# Solenoid_9.net
KiCad netlist of a schematic drawn in EAGLE
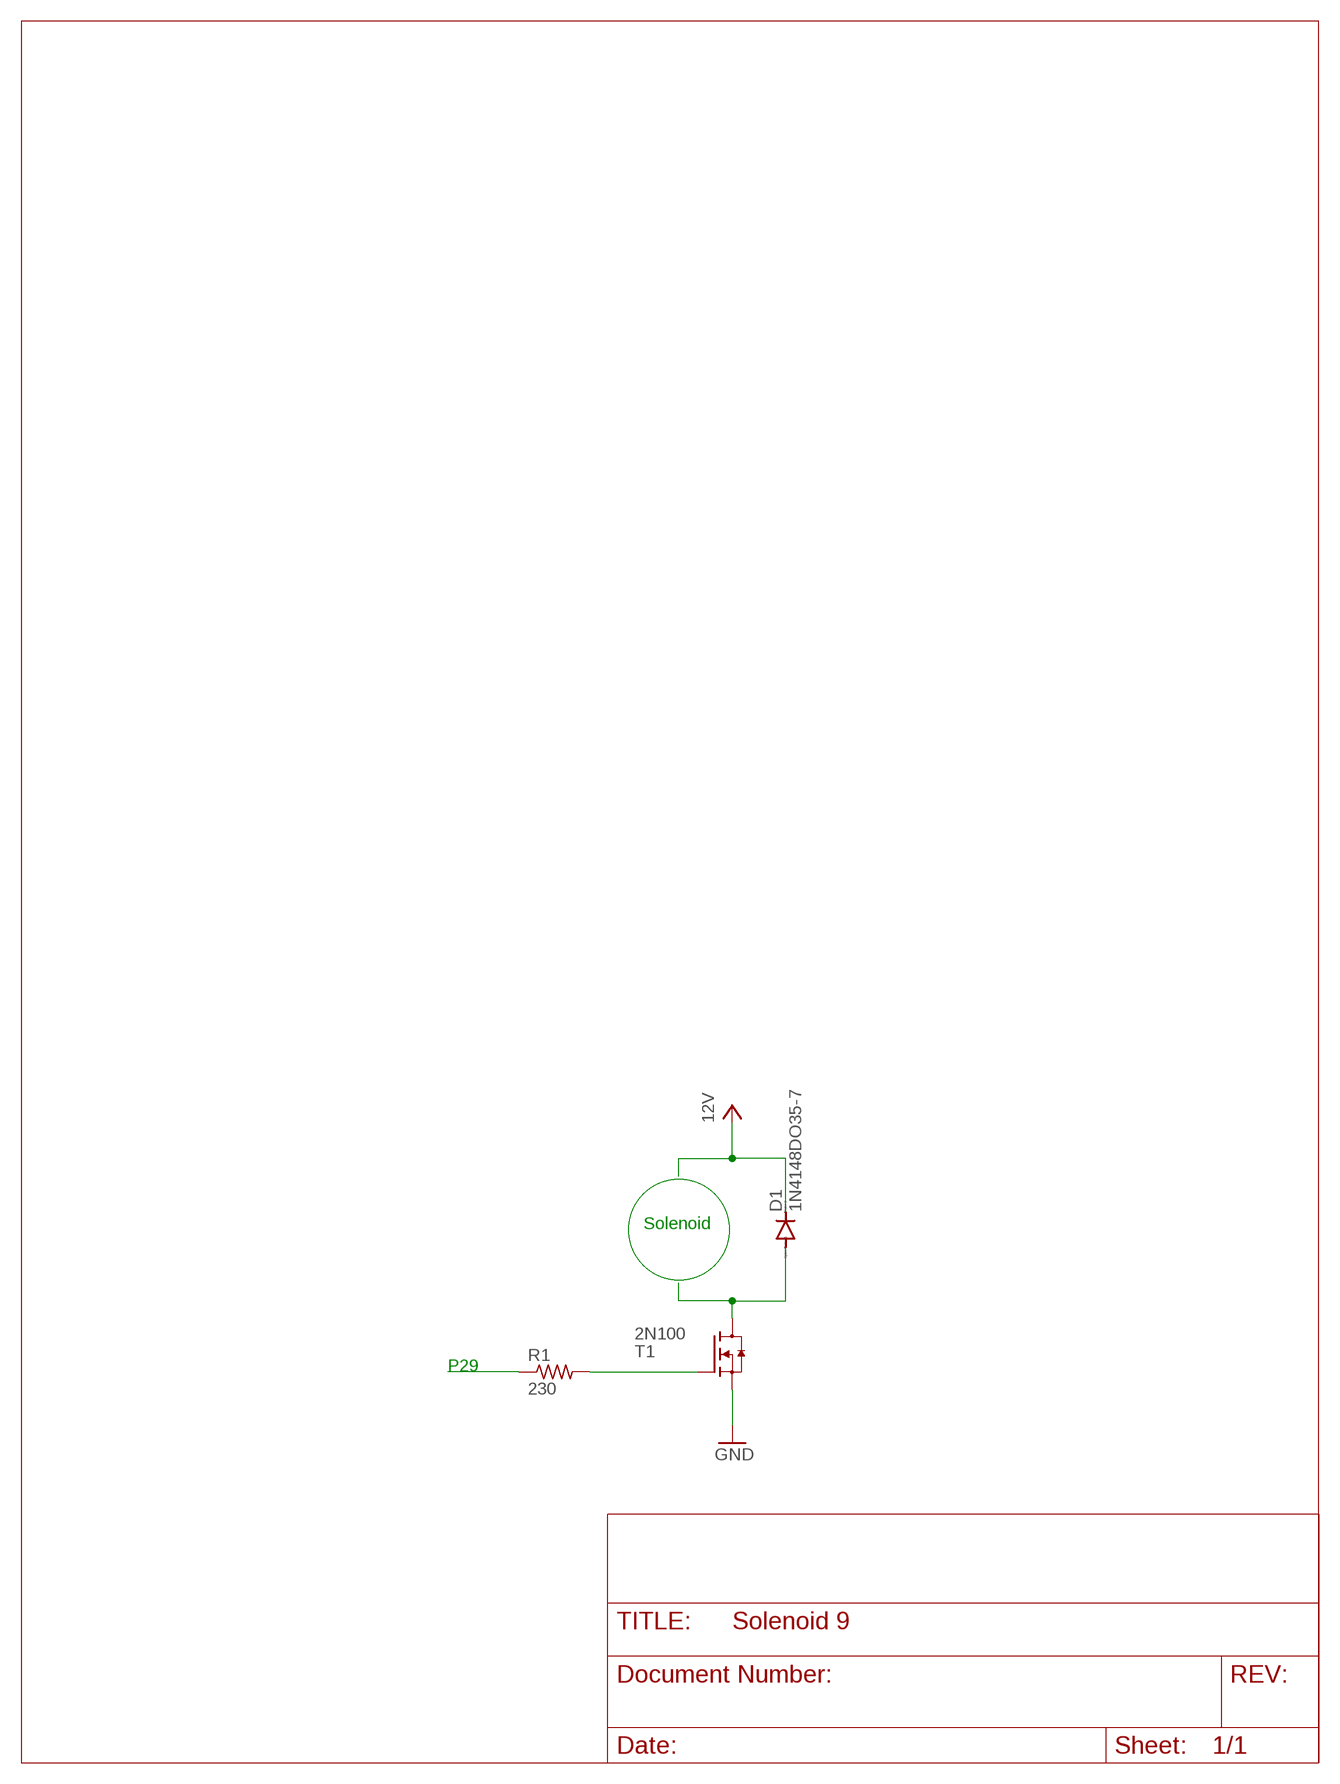
[diagram p0: schematic, sheet 1]

(export (version "E")
  (design (tool "Eeschema 10.0.6"))
  (components
    (comp (ref "D1")
      (value "1N4148DO35-7")
      (footprint "eagle-import:DO35-7")
      (libsource (lib "eagle-import") (part "1N4148DO35-7"))
    )
    (comp (ref "R1")
      (value "230")
      (footprint "eagle-import:0204_7")
      (libsource (lib "eagle-import") (part "R-US_0204/7"))
    )
    (comp (ref "T1")
      (value "2N100")
      (footprint "eagle-import:PG-TO263-7-3")
      (libsource (lib "eagle-import") (part "IPB180N06S4-H1"))
    )
  )
  (nets
    (net (code "1") (name "12V") (class "Default")
      (node (ref "D1") (pin "C") (pinfunction "C_C") (pintype "passive"))
    )
    (net (code "2") (name "GND") (class "Default")
      (node (ref "T1") (pin "2") (pinfunction "S_2") (pintype "passive"))
      (node (ref "T1") (pin "3") (pinfunction "S_3") (pintype "passive"))
      (node (ref "T1") (pin "5") (pinfunction "S_5") (pintype "passive"))
      (node (ref "T1") (pin "6") (pinfunction "S_6") (pintype "passive"))
      (node (ref "T1") (pin "7") (pinfunction "S_7") (pintype "passive"))
    )
    (net (code "3") (name "Net-(T1-D)") (class "Default")
      (node (ref "D1") (pin "A") (pinfunction "A_A") (pintype "passive"))
      (node (ref "T1") (pin "8") (pinfunction "D_8") (pintype "passive"))
    )
    (net (code "4") (name "Net-(T1-G)") (class "Default")
      (node (ref "R1") (pin "2") (pinfunction "2_2") (pintype "passive"))
      (node (ref "T1") (pin "1") (pinfunction "G_1") (pintype "passive"))
    )
    (net (code "5") (name "unconnected-(R1-Pad1)") (class "Default")
      (node (ref "R1") (pin "1") (pinfunction "1_1") (pintype "passive"))
    )
  )
)
